# DB_LEDS_0603.net
KiCad netlist of a schematic drawn in Altium Designer
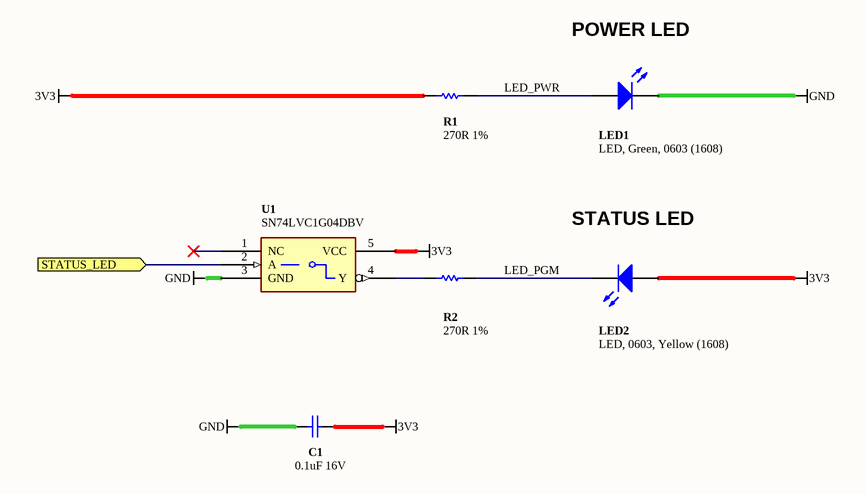
[diagram p0: DB_LEDS_0603.SchDoc]

(export (version "E")
  (design (tool "Eeschema 10.0.6"))
  (components
    (comp (ref "C1")
      (value "0.1uF 16V")
      (footprint "CAPC1005-STAR")
      (description "Capacitor, Ceramic, 0.1uF 10% 16V 0402 (1005) X7R")
      (fields (field (name "TOLERANCE") "10 %"))
      (libsource (lib "AltiumDesignLibrary") (part "CAP-NP"))
    )
    (comp (ref "LED1")
      (value "LED, Green, 0603 (1608)")
      (footprint "0603LED_GREEN")
      (libsource (lib "AltiumDesignLibrary") (part "DIO-LED-1S"))
    )
    (comp (ref "LED2")
      (value "LED, 0603, Yellow (1608)")
      (footprint "0603LED_YELLOW")
      (libsource (lib "AltiumDesignLibrary") (part "DIO-LED-1S"))
    )
    (comp (ref "R1")
      (value "270R 1%")
      (footprint "RESC1005-STAR")
      (description "Resistor, 270R 1% 0402 (1005)")
      (fields (field (name "TOLERANCE") "1 %"))
      (libsource (lib "AltiumDesignLibrary") (part "RES"))
    )
    (comp (ref "R2")
      (value "270R 1%")
      (footprint "RESC1005-STAR")
      (description "Resistor, 270R 1% 0402 (1005)")
      (fields (field (name "TOLERANCE") "1 %"))
      (libsource (lib "AltiumDesignLibrary") (part "RES"))
    )
    (comp (ref "U1")
      (value "SN74LVC1G04DBV")
      (footprint "SOT95P280-5")
      (description "SN74LVC1G04DBV, Single Inverter Gate, 1.65-V to 5.5-V")
      (libsource (lib "AltiumDesignLibrary") (part "SN74LVC1G04DBV"))
    )
  )
  (nets
    (net (code "1") (name "/LED_PGM") (class "Default")
      (node (ref "LED2") (pin "2") (pinfunction "K_2") (pintype "passive"))
      (node (ref "R2") (pin "2") (pinfunction "2_2") (pintype "passive"))
    )
    (net (code "2") (name "/LED_PWR") (class "Default")
      (node (ref "LED1") (pin "1") (pinfunction "A_1") (pintype "passive"))
      (node (ref "R1") (pin "2") (pinfunction "2_2") (pintype "passive"))
    )
    (net (code "3") (name "/STATUS_LED") (class "Default")
      (node (ref "U1") (pin "2") (pinfunction "A_2") (pintype "input"))
    )
    (net (code "4") (name "3V3") (class "Default")
      (node (ref "C1") (pin "2") (pinfunction "2_2") (pintype "passive"))
      (node (ref "LED2") (pin "1") (pinfunction "A_1") (pintype "passive"))
      (node (ref "R1") (pin "1") (pinfunction "1_1") (pintype "passive"))
      (node (ref "U1") (pin "5") (pinfunction "VCC_5") (pintype "power_in"))
    )
    (net (code "5") (name "GND") (class "Default")
      (node (ref "C1") (pin "1") (pinfunction "1_1") (pintype "passive"))
      (node (ref "LED1") (pin "2") (pinfunction "K_2") (pintype "passive"))
      (node (ref "U1") (pin "3") (pinfunction "GND_3") (pintype "power_in"))
    )
    (net (code "6") (name "Net-(U1-Y)") (class "Default")
      (node (ref "R2") (pin "1") (pinfunction "1_1") (pintype "passive"))
      (node (ref "U1") (pin "4") (pinfunction "Y_4") (pintype "output"))
    )
    (net (code "7") (name "unconnected-(U1-NC-Pad1)") (class "Default")
      (node (ref "U1") (pin "1") (pinfunction "NC_1") (pintype "passive+no_connect"))
    )
  )
)
